# diode.net
KiCad netlist of a schematic drawn in EAGLE
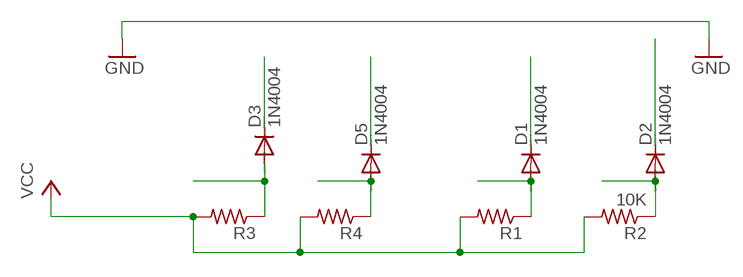
[diagram p0: schematic, sheet 1]

(export (version "E")
  (design (tool "Eeschema 10.0.6"))
  (components
    (comp (ref "D1")
      (value "1N4004")
      (footprint "eagle-import:DO41-10")
      (libsource (lib "eagle-import") (part "1N4004"))
    )
    (comp (ref "D2")
      (value "1N4004")
      (footprint "eagle-import:DO41-10")
      (libsource (lib "eagle-import") (part "1N4004"))
    )
    (comp (ref "D3")
      (value "1N4004")
      (footprint "eagle-import:DO41-10")
      (libsource (lib "eagle-import") (part "1N4004"))
    )
    (comp (ref "D5")
      (value "1N4004")
      (footprint "eagle-import:DO41-10")
      (libsource (lib "eagle-import") (part "1N4004"))
    )
    (comp (ref "R1")
      (value "R-US_0204/5")
      (footprint "eagle-import:0204_5")
      (libsource (lib "eagle-import") (part "R-US_0204/5"))
    )
    (comp (ref "R2")
      (value "10K")
      (footprint "eagle-import:0204_5")
      (libsource (lib "eagle-import") (part "R-US_0204/5"))
    )
    (comp (ref "R3")
      (value "R-US_0204/5")
      (footprint "eagle-import:0204_5")
      (libsource (lib "eagle-import") (part "R-US_0204/5"))
    )
    (comp (ref "R4")
      (value "R-US_0204/5")
      (footprint "eagle-import:0204_5")
      (libsource (lib "eagle-import") (part "R-US_0204/5"))
    )
  )
  (nets
    (net (code "2") (name "Net-(D1-PadA)") (class "Default")
      (node (ref "D1") (pin "A") (pinfunction "A_A") (pintype "passive"))
      (node (ref "R1") (pin "1") (pinfunction "1_1") (pintype "passive"))
    )
    (net (code "3") (name "Net-(D2-PadA)") (class "Default")
      (node (ref "D2") (pin "A") (pinfunction "A_A") (pintype "passive"))
      (node (ref "R2") (pin "1") (pinfunction "1_1") (pintype "passive"))
    )
    (net (code "4") (name "Net-(D3-PadA)") (class "Default")
      (node (ref "D3") (pin "A") (pinfunction "A_A") (pintype "passive"))
      (node (ref "R3") (pin "1") (pinfunction "1_1") (pintype "passive"))
    )
    (net (code "5") (name "Net-(D5-PadA)") (class "Default")
      (node (ref "D5") (pin "A") (pinfunction "A_A") (pintype "passive"))
      (node (ref "R4") (pin "1") (pinfunction "1_1") (pintype "passive"))
    )
    (net (code "6") (name "VCC") (class "Default")
      (node (ref "R1") (pin "2") (pinfunction "2_2") (pintype "passive"))
      (node (ref "R2") (pin "2") (pinfunction "2_2") (pintype "passive"))
      (node (ref "R3") (pin "2") (pinfunction "2_2") (pintype "passive"))
      (node (ref "R4") (pin "2") (pinfunction "2_2") (pintype "passive"))
    )
    (net (code "7") (name "unconnected-(D1-PadC)") (class "Default")
      (node (ref "D1") (pin "C") (pinfunction "C_C") (pintype "passive"))
    )
    (net (code "8") (name "unconnected-(D2-PadC)") (class "Default")
      (node (ref "D2") (pin "C") (pinfunction "C_C") (pintype "passive"))
    )
    (net (code "9") (name "unconnected-(D3-PadC)") (class "Default")
      (node (ref "D3") (pin "C") (pinfunction "C_C") (pintype "passive"))
    )
    (net (code "10") (name "unconnected-(D5-PadC)") (class "Default")
      (node (ref "D5") (pin "C") (pinfunction "C_C") (pintype "passive"))
    )
  )
)
